# 3v3_linear_power.net
KiCad netlist of a schematic drawn in Altium Designer
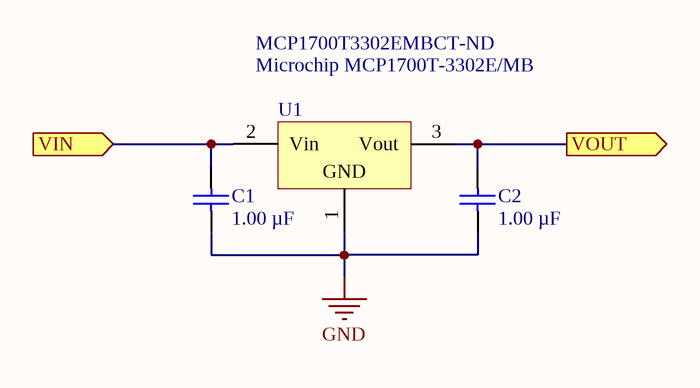
[diagram p0: 3v3_linear_power.SchDoc]

(export (version "E")
  (design (tool "Eeschema 10.0.6"))
  (components
    (comp (ref "C1")
      (value "Würth Elektronik 885012207051")
      (footprint "PCB-xrh88671zmf2jss4mnlt-1")
      (description "Capacitor [Würth Elektronik] 885012207051 Capacitor")
      (fields (field (name "MANUFACTURER PART NUMBER") "885012207051") (field (name "CAPACITANCE") "1.00 µF"))
      (libsource (lib "CommunityVault") (part "CMP-7104bbe86e53aec3-1"))
    )
    (comp (ref "C2")
      (value "Würth Elektronik 885012207051")
      (footprint "PCB-xrh88671zmf2jss4mnlt-1")
      (description "Capacitor [Würth Elektronik] 885012207051 Capacitor")
      (fields (field (name "MANUFACTURER PART NUMBER") "885012207051") (field (name "CAPACITANCE") "1.00 µF"))
      (libsource (lib "CommunityVault") (part "CMP-7104bbe86e53aec3-1"))
    )
    (comp (ref "U1")
      (value "Microchip MCP1700T-3302E/MB")
      (footprint "SOT-89-MB3_L")
      (description "LDO voltage regulator [Microchip] MCP1700T-3302E/MB LDO voltage regulator")
      (libsource (lib "CommunityVault") (part "SYM-54ee9dec78a18b29-1"))
    )
  )
  (nets
    (net (code "1") (name "/VIN") (class "Default")
      (node (ref "C1") (pin "2") (pinfunction "2_2") (pintype "passive"))
      (node (ref "U1") (pin "2") (pinfunction "Vin_2") (pintype "power_in"))
    )
    (net (code "2") (name "/VOUT") (class "Default")
      (node (ref "C2") (pin "2") (pinfunction "2_2") (pintype "passive"))
      (node (ref "U1") (pin "3") (pinfunction "Vout_3") (pintype "power_in"))
    )
    (net (code "3") (name "GND") (class "Default")
      (node (ref "C1") (pin "1") (pinfunction "1_1") (pintype "passive"))
      (node (ref "C2") (pin "1") (pinfunction "1_1") (pintype "passive"))
      (node (ref "U1") (pin "1") (pinfunction "GND_1") (pintype "power_in"))
    )
  )
)
